# Steckkarte.net
KiCad netlist of a schematic drawn in EAGLE
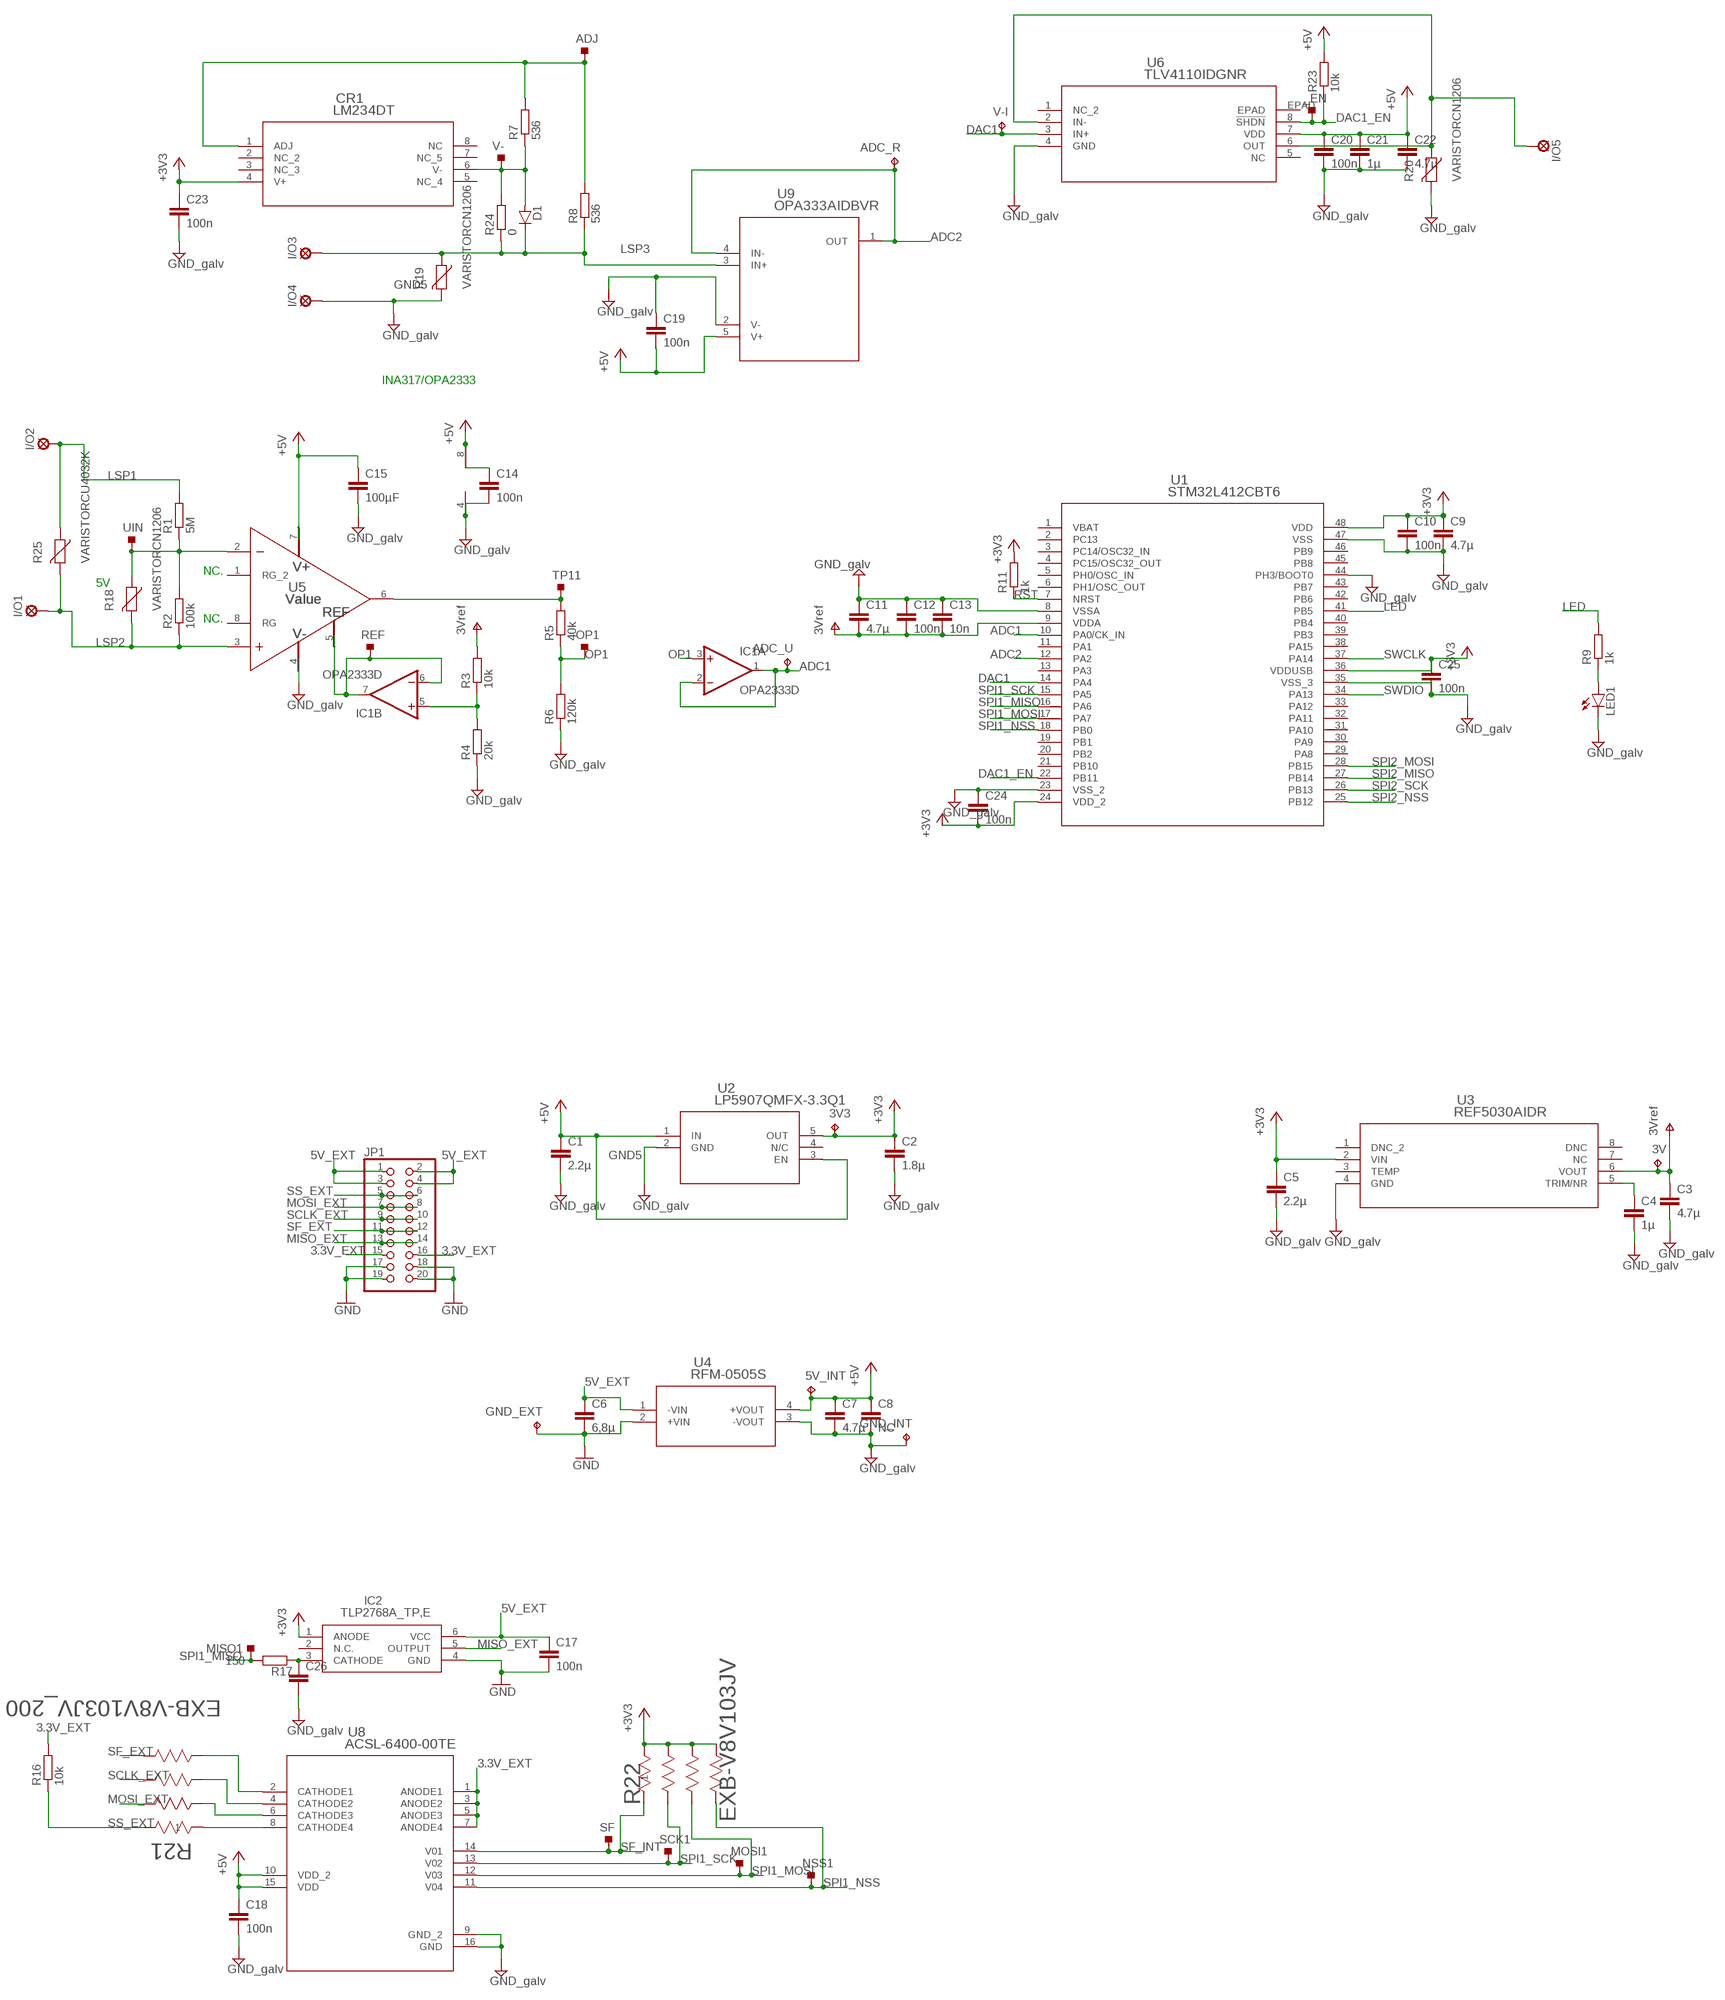
[diagram p0: schematic, sheet 1, part 1 of 2]
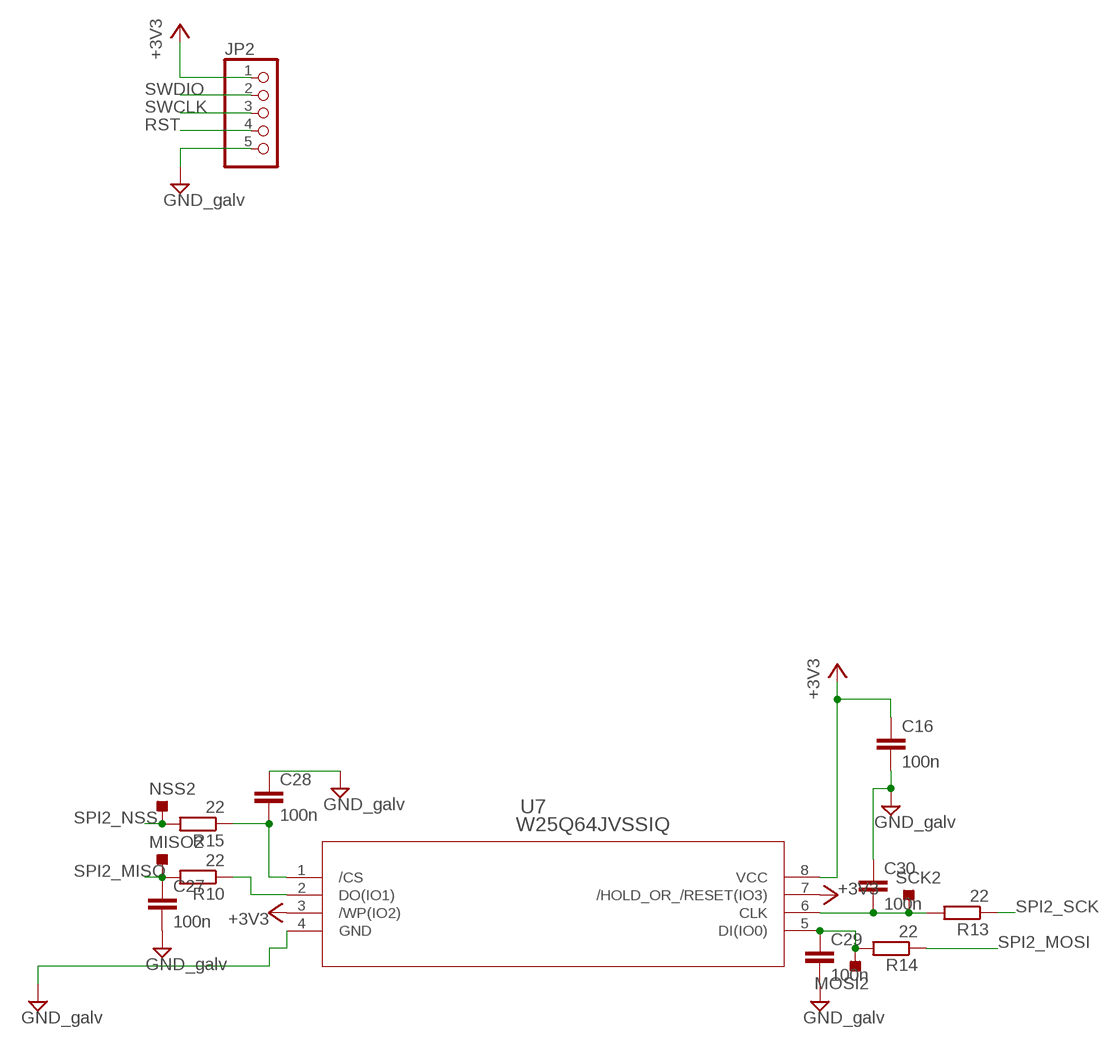
[diagram p1: schematic, sheet 1, part 2 of 2]

(export (version "E")
  (design (tool "Eeschema 10.0.6"))
  (components
    (comp (ref "3V")
      (value "TPPAD1-13")
      (footprint "eagle-import:P1-13")
      (libsource (lib "eagle-import") (part "TPPAD1-13"))
    )
    (comp (ref "3V3")
      (value "TPPAD1-13")
      (footprint "eagle-import:P1-13")
      (libsource (lib "eagle-import") (part "TPPAD1-13"))
    )
    (comp (ref "5V_INT")
      (value "TPPAD1-13")
      (footprint "eagle-import:P1-13")
      (libsource (lib "eagle-import") (part "TPPAD1-13"))
    )
    (comp (ref "ADC_R")
      (value "TPPAD1-13")
      (footprint "eagle-import:P1-13")
      (libsource (lib "eagle-import") (part "TPPAD1-13"))
    )
    (comp (ref "ADC_U")
      (value "TPPAD1-13")
      (footprint "eagle-import:P1-13")
      (libsource (lib "eagle-import") (part "TPPAD1-13"))
    )
    (comp (ref "ADJ")
      (value "TESTPOINT_TPS-SMD-10SN")
      (footprint "eagle-import:TESTPOINT_SMD-10SN")
      (libsource (lib "eagle-import") (part "TESTPOINT_TPS-SMD-10SN"))
    )
    (comp (ref "C1")
      (value "2.2µ")
      (footprint "eagle-import:C0603K")
      (libsource (lib "eagle-import") (part "C-EUC0603K"))
    )
    (comp (ref "C2")
      (value "1.8µ")
      (footprint "eagle-import:C1206K")
      (libsource (lib "eagle-import") (part "C-EUC1206K"))
    )
    (comp (ref "C3")
      (value "4.7µ")
      (footprint "eagle-import:C0603K")
      (libsource (lib "eagle-import") (part "C-EUC0603K"))
    )
    (comp (ref "C4")
      (value "1µ")
      (footprint "eagle-import:C0603K")
      (libsource (lib "eagle-import") (part "C-EUC0603K"))
    )
    (comp (ref "C5")
      (value "2.2µ")
      (footprint "eagle-import:C0603K")
      (libsource (lib "eagle-import") (part "C-EUC0603K"))
    )
    (comp (ref "C6")
      (value "6,8µ")
      (footprint "eagle-import:C0603K")
      (libsource (lib "eagle-import") (part "resistor_348_C-EUC0603K"))
    )
    (comp (ref "C7")
      (value "4.7µ")
      (footprint "eagle-import:C0603K")
      (libsource (lib "eagle-import") (part "resistor_348_C-EUC0603K"))
    )
    (comp (ref "C8")
      (value "NC")
      (footprint "eagle-import:C0603K")
      (libsource (lib "eagle-import") (part "resistor_348_C-EUC0603K"))
    )
    (comp (ref "C9")
      (value "4.7µ")
      (footprint "eagle-import:C0603K")
      (libsource (lib "eagle-import") (part "C-EUC0603K"))
    )
    (comp (ref "C10")
      (value "100n")
      (footprint "eagle-import:C0603K")
      (libsource (lib "eagle-import") (part "C-EUC0603K"))
    )
    (comp (ref "C11")
      (value "4.7µ")
      (footprint "eagle-import:C0603K")
      (libsource (lib "eagle-import") (part "C-EUC0603K"))
    )
    (comp (ref "C12")
      (value "100n")
      (footprint "eagle-import:C0603K")
      (libsource (lib "eagle-import") (part "C-EUC0603K"))
    )
    (comp (ref "C13")
      (value "10n")
      (footprint "eagle-import:C0603K")
      (libsource (lib "eagle-import") (part "C-EUC0603K"))
    )
    (comp (ref "C14")
      (value "100n")
      (footprint "eagle-import:C0603K")
      (libsource (lib "eagle-import") (part "C-EUC0603K"))
    )
    (comp (ref "C15")
      (value "100µF")
      (footprint "eagle-import:C1206K")
      (libsource (lib "eagle-import") (part "resistor_348_C-EUC1206K"))
    )
    (comp (ref "C16")
      (value "100n")
      (footprint "eagle-import:C0603K")
      (libsource (lib "eagle-import") (part "C-EUC0603K"))
    )
    (comp (ref "C17")
      (value "100n")
      (footprint "eagle-import:C0603K")
      (libsource (lib "eagle-import") (part "C-EUC0603K"))
    )
    (comp (ref "C18")
      (value "100n")
      (footprint "eagle-import:C0603K")
      (libsource (lib "eagle-import") (part "C-EUC0603K"))
    )
    (comp (ref "C19")
      (value "100n")
      (footprint "eagle-import:C0603K")
      (libsource (lib "eagle-import") (part "C-EUC0603K"))
    )
    (comp (ref "C20")
      (value "100n")
      (footprint "eagle-import:C0603K")
      (libsource (lib "eagle-import") (part "C-EUC0603K"))
    )
    (comp (ref "C21")
      (value "1µ")
      (footprint "eagle-import:C0603K")
      (libsource (lib "eagle-import") (part "C-EUC0603K"))
    )
    (comp (ref "C22")
      (value "4.7µ")
      (footprint "eagle-import:C0603K")
      (libsource (lib "eagle-import") (part "C-EUC0603K"))
    )
    (comp (ref "C23")
      (value "100n")
      (footprint "eagle-import:C0603K")
      (libsource (lib "eagle-import") (part "C-EUC0603K"))
    )
    (comp (ref "C24")
      (value "100n")
      (footprint "eagle-import:C0603K")
      (libsource (lib "eagle-import") (part "C-EUC0603K"))
    )
    (comp (ref "C25")
      (value "100n")
      (footprint "eagle-import:C0603K")
      (libsource (lib "eagle-import") (part "C-EUC0603K"))
    )
    (comp (ref "C26")
      (value "C-EUC0603K")
      (footprint "eagle-import:C0603K")
      (libsource (lib "eagle-import") (part "C-EUC0603K"))
    )
    (comp (ref "C27")
      (value "100n")
      (footprint "eagle-import:C0603K")
      (libsource (lib "eagle-import") (part "C-EUC0603K"))
    )
    (comp (ref "C28")
      (value "100n")
      (footprint "eagle-import:C0603K")
      (libsource (lib "eagle-import") (part "C-EUC0603K"))
    )
    (comp (ref "C29")
      (value "100n")
      (footprint "eagle-import:C0603K")
      (libsource (lib "eagle-import") (part "C-EUC0603K"))
    )
    (comp (ref "C30")
      (value "100n")
      (footprint "eagle-import:C0603K")
      (libsource (lib "eagle-import") (part "C-EUC0603K"))
    )
    (comp (ref "CR1")
      (value "LM234DT")
      (footprint "eagle-import:SO-8")
      (libsource (lib "eagle-import") (part "LM234DT"))
    )
    (comp (ref "D1")
      (value "D-SOD123")
      (footprint "eagle-import:SOD123")
      (libsource (lib "eagle-import") (part "D-SOD123"))
    )
    (comp (ref "GND_EXT")
      (value "TPPAD1-13")
      (footprint "eagle-import:P1-13")
      (libsource (lib "eagle-import") (part "TPPAD1-13"))
    )
    (comp (ref "GND_INT")
      (value "TPPAD1-13")
      (footprint "eagle-import:P1-13")
      (libsource (lib "eagle-import") (part "TPPAD1-13"))
    )
    (comp (ref "I/O1")
      (value "SE14")
      (footprint "eagle-import:SE14")
      (libsource (lib "eagle-import") (part "SE14"))
    )
    (comp (ref "I/O2")
      (value "SE14")
      (footprint "eagle-import:SE14")
      (libsource (lib "eagle-import") (part "SE14"))
    )
    (comp (ref "I/O3")
      (value "SE14")
      (footprint "eagle-import:SE14")
      (libsource (lib "eagle-import") (part "SE14"))
    )
    (comp (ref "I/O4")
      (value "SE14")
      (footprint "eagle-import:SE14")
      (libsource (lib "eagle-import") (part "SE14"))
    )
    (comp (ref "I/O5")
      (value "SE14")
      (footprint "eagle-import:SE14")
      (libsource (lib "eagle-import") (part "SE14"))
    )
    (comp (ref "IC1")
      (value "OPA2333D")
      (footprint "eagle-import:SO08")
      (libsource (lib "eagle-import") (part "OPA2333D"))
    )
    (comp (ref "IC2")
      (value "TLP2768A_TP,E")
      (footprint "eagle-import:SOIC127P1000X220-6N")
      (fields
        (field (name "MANUFACTURER_PART_NUMBER") "TLP2768A(TP,E")
        (field (name "MOUSER_PART_NUMBER") "757-TLP2768ATPE")
      )
      (libsource (lib "eagle-import") (part "TLP2768A_TP,E"))
    )
    (comp (ref "JP1")
      (value "PINHD-2X10/90")
      (footprint "eagle-import:2X10_90")
      (libsource (lib "eagle-import") (part "PINHD-2X10/90"))
    )
    (comp (ref "JP2")
      (value "PINHD-1X5")
      (footprint "eagle-import:1X05")
      (libsource (lib "eagle-import") (part "PINHD-1X5"))
    )
    (comp (ref "LED1")
      (value "LED5MM")
      (footprint "eagle-import:LED5MM")
      (libsource (lib "eagle-import") (part "LED5MM"))
    )
    (comp (ref "MISO1")
      (value "TESTPOINT_TPS-SMD-10SN")
      (footprint "eagle-import:TESTPOINT_SMD-10SN")
      (libsource (lib "eagle-import") (part "TESTPOINT_TPS-SMD-10SN"))
    )
    (comp (ref "MISO2")
      (value "TESTPOINT_TPS-SMD-10SN")
      (footprint "eagle-import:TESTPOINT_SMD-10SN")
      (libsource (lib "eagle-import") (part "TESTPOINT_TPS-SMD-10SN"))
    )
    (comp (ref "MOSI1")
      (value "TESTPOINT_TPS-SMD-10SN")
      (footprint "eagle-import:TESTPOINT_SMD-10SN")
      (libsource (lib "eagle-import") (part "TESTPOINT_TPS-SMD-10SN"))
    )
    (comp (ref "MOSI2")
      (value "TESTPOINT_TPS-SMD-10SN")
      (footprint "eagle-import:TESTPOINT_SMD-10SN")
      (libsource (lib "eagle-import") (part "TESTPOINT_TPS-SMD-10SN"))
    )
    (comp (ref "NSS1")
      (value "TESTPOINT_TPS-SMD-10SN")
      (footprint "eagle-import:TESTPOINT_SMD-10SN")
      (libsource (lib "eagle-import") (part "TESTPOINT_TPS-SMD-10SN"))
    )
    (comp (ref "NSS2")
      (value "TESTPOINT_TPS-SMD-10SN")
      (footprint "eagle-import:TESTPOINT_SMD-10SN")
      (libsource (lib "eagle-import") (part "TESTPOINT_TPS-SMD-10SN"))
    )
    (comp (ref "OP1")
      (value "TESTPOINT_TPS-SMD-10SN")
      (footprint "eagle-import:TESTPOINT_SMD-10SN")
      (libsource (lib "eagle-import") (part "TESTPOINT_TPS-SMD-10SN"))
    )
    (comp (ref "R1")
      (value "5M")
      (footprint "eagle-import:R1206")
      (libsource (lib "eagle-import") (part "R-EU_R1206"))
    )
    (comp (ref "R2")
      (value "100k")
      (footprint "eagle-import:R1206")
      (libsource (lib "eagle-import") (part "R-EU_R1206"))
    )
    (comp (ref "R3")
      (value "10k")
      (footprint "eagle-import:R0603")
      (libsource (lib "eagle-import") (part "R-EU_R0603"))
    )
    (comp (ref "R4")
      (value "20k")
      (footprint "eagle-import:R0603")
      (libsource (lib "eagle-import") (part "R-EU_R0603"))
    )
    (comp (ref "R5")
      (value "40k")
      (footprint "eagle-import:R0603")
      (libsource (lib "eagle-import") (part "R-EU_R0603"))
    )
    (comp (ref "R6")
      (value "120k")
      (footprint "eagle-import:R0603")
      (libsource (lib "eagle-import") (part "R-EU_R0603"))
    )
    (comp (ref "R7")
      (value "536")
      (footprint "eagle-import:R0603")
      (libsource (lib "eagle-import") (part "R-EU_R0603"))
    )
    (comp (ref "R8")
      (value "536")
      (footprint "eagle-import:R0603")
      (libsource (lib "eagle-import") (part "R-EU_R0603"))
    )
    (comp (ref "R9")
      (value "1k")
      (footprint "eagle-import:R0603")
      (libsource (lib "eagle-import") (part "R-EU_R0603"))
    )
    (comp (ref "R10")
      (value "22")
      (footprint "eagle-import:R0603")
      (libsource (lib "eagle-import") (part "R-EU_R0603"))
    )
    (comp (ref "R11")
      (value "1k")
      (footprint "eagle-import:R0603")
      (libsource (lib "eagle-import") (part "R-EU_R0603"))
    )
    (comp (ref "R13")
      (value "22")
      (footprint "eagle-import:R0603")
      (libsource (lib "eagle-import") (part "R-EU_R0603"))
    )
    (comp (ref "R14")
      (value "22")
      (footprint "eagle-import:R0603")
      (libsource (lib "eagle-import") (part "R-EU_R0603"))
    )
    (comp (ref "R15")
      (value "22")
      (footprint "eagle-import:R0603")
      (libsource (lib "eagle-import") (part "R-EU_R0603"))
    )
    (comp (ref "R16")
      (value "10k")
      (footprint "eagle-import:R0603")
      (libsource (lib "eagle-import") (part "R-EU_R0603"))
    )
    (comp (ref "R17")
      (value "150")
      (footprint "eagle-import:R0603")
      (libsource (lib "eagle-import") (part "R-EU_R0603"))
    )
    (comp (ref "R18")
      (value "VARISTORCN1206")
      (footprint "eagle-import:CT_CN1206")
      (libsource (lib "eagle-import") (part "VARISTORCN1206"))
    )
    (comp (ref "R19")
      (value "VARISTORCN1206")
      (footprint "eagle-import:CT_CN1206")
      (libsource (lib "eagle-import") (part "VARISTORCN1206"))
    )
    (comp (ref "R20")
      (value "VARISTORCN1206")
      (footprint "eagle-import:CT_CN1206")
      (libsource (lib "eagle-import") (part "VARISTORCN1206"))
    )
    (comp (ref "R21")
      (value "EXB-V8V103JV_200")
      (footprint "eagle-import:EXBV8V")
      (fields (field (name "MANUFACTURER_PART_NUMBER") "EXB-V8V103JV"))
      (libsource (lib "eagle-import") (part "EXB-V8V103JV"))
    )
    (comp (ref "R22")
      (value "EXB-V8V103JV")
      (footprint "eagle-import:EXBV8V")
      (libsource (lib "eagle-import") (part "EXB-V8V103JV"))
    )
    (comp (ref "R23")
      (value "10k")
      (footprint "eagle-import:R0603")
      (libsource (lib "eagle-import") (part "R-EU_R0603"))
    )
    (comp (ref "R24")
      (value "0")
      (footprint "eagle-import:R0603")
      (libsource (lib "eagle-import") (part "R-EU_R0603"))
    )
    (comp (ref "R25")
      (value "VARISTORCU4032K")
      (footprint "eagle-import:CU4032K")
      (libsource (lib "eagle-import") (part "VARISTORCU4032K"))
    )
    (comp (ref "REF")
      (value "TESTPOINT_TPS-SMD-10SN")
      (footprint "eagle-import:TESTPOINT_SMD-10SN")
      (libsource (lib "eagle-import") (part "TESTPOINT_TPS-SMD-10SN"))
    )
    (comp (ref "SCK1")
      (value "TESTPOINT_TPS-SMD-10SN")
      (footprint "eagle-import:TESTPOINT_SMD-10SN")
      (libsource (lib "eagle-import") (part "TESTPOINT_TPS-SMD-10SN"))
    )
    (comp (ref "SCK2")
      (value "TESTPOINT_TPS-SMD-10SN")
      (footprint "eagle-import:TESTPOINT_SMD-10SN")
      (libsource (lib "eagle-import") (part "TESTPOINT_TPS-SMD-10SN"))
    )
    (comp (ref "SF")
      (value "TESTPOINT_TPS-SMD-10SN")
      (footprint "eagle-import:TESTPOINT_SMD-10SN")
      (libsource (lib "eagle-import") (part "TESTPOINT_TPS-SMD-10SN"))
    )
    (comp (ref "TP11")
      (value "TESTPOINT_TPS-SMD-10SN")
      (footprint "eagle-import:TESTPOINT_SMD-10SN")
      (libsource (lib "eagle-import") (part "TESTPOINT_TPS-SMD-10SN"))
    )
    (comp (ref "U1")
      (value "STM32L412CBT6")
      (footprint "eagle-import:LQFP-48")
      (fields (field (name "COPYRIGHT") "Copyright (C) 2018 Accelerated Designs. All rights reserved"))
      (libsource (lib "eagle-import") (part "STM32L412CBT6"))
    )
    (comp (ref "U2")
      (value "LP5907QMFX-3.3Q1")
      (footprint "eagle-import:DBV5")
      (libsource (lib "eagle-import") (part "LP5907QMFX-3.3Q1"))
    )
    (comp (ref "U3")
      (value "REF5030AIDR")
      (footprint "eagle-import:D8")
      (libsource (lib "eagle-import") (part "REF5030AIDR"))
    )
    (comp (ref "U4")
      (value "RFM-0505S")
      (footprint "eagle-import:RFM-0505S")
      (fields (field (name "COPYRIGHT") "Copyright (C) 2018 Accelerated Designs. All rights reserved"))
      (libsource (lib "eagle-import") (part "RFM-0505S"))
    )
    (comp (ref "U5")
      (value "Value")
      (footprint "eagle-import:DGK0008A_N")
      (fields (field (name "MANUFACTURER") "Texas Instruments") (field (name "PARTNUMBER") "INA317IDGKR"))
      (libsource (lib "eagle-import") (part "INA317IDGKR"))
    )
    (comp (ref "U6")
      (value "TLV4110IDGNR")
      (footprint "eagle-import:DGN8_1P89X1P57")
      (fields
        (field (name "GENERIC_PART_NUMBER") "TLV4110")
        (field (name "MANUFACTURER") "Texas Instruments")
      )
      (libsource (lib "eagle-import") (part "TLV4110IDGNR"))
    )
    (comp (ref "U7")
      (value "W25Q64JVSSIQ")
      (footprint "eagle-import:SOIC-8_5P28X5P28")
      (fields (field (name "COPYRIGHT") "Copyright (C) 2018 Accelerated Designs. All rights reserved"))
      (libsource (lib "eagle-import") (part "W25Q64JVSSIQ"))
    )
    (comp (ref "U8")
      (value "ACSL-6400-00TE")
      (footprint "eagle-import:SOIC_6400-00TE")
      (fields (field (name "COPYRIGHT") "Copyright (C) 2018 Accelerated Designs. All rights reserved"))
      (libsource (lib "eagle-import") (part "ACSL-6400-00TE"))
    )
    (comp (ref "U9")
      (value "OPA333AIDBVR")
      (footprint "eagle-import:DBV5")
      (fields (field (name "GENERIC_PART_NUMBER") "OPA333") (field (name "MANUFACTURER") "Texas Instruments"))
      (libsource (lib "eagle-import") (part "OPA333AIDBVR"))
    )
    (comp (ref "UIN")
      (value "TESTPOINT_TPS-SMD-10SN")
      (footprint "eagle-import:TESTPOINT_SMD-10SN")
      (libsource (lib "eagle-import") (part "TESTPOINT_TPS-SMD-10SN"))
    )
    (comp (ref "V-")
      (value "TESTPOINT_TPS-SMD-10SN")
      (footprint "eagle-import:TESTPOINT_SMD-10SN")
      (libsource (lib "eagle-import") (part "TESTPOINT_TPS-SMD-10SN"))
    )
    (comp (ref "V-I")
      (value "TPPAD1-13")
      (footprint "eagle-import:P1-13")
      (libsource (lib "eagle-import") (part "TPPAD1-13"))
    )
    (comp (ref "_EN")
      (value "TESTPOINT_TPS-SMD-10SN")
      (footprint "eagle-import:TESTPOINT_SMD-10SN")
      (libsource (lib "eagle-import") (part "TESTPOINT_TPS-SMD-10SN"))
    )
  )
  (nets
    (net (code "1") (name "+3V3") (class "Default")
      (node (ref "3V3") (pin "TP") (pinfunction "TP_TP") (pintype "input"))
      (node (ref "C10") (pin "1") (pinfunction "1_1") (pintype "passive"))
      (node (ref "C16") (pin "1") (pinfunction "1_1") (pintype "passive"))
      (node (ref "C2") (pin "1") (pinfunction "1_1") (pintype "passive"))
      (node (ref "C23") (pin "1") (pinfunction "1_1") (pintype "passive"))
      (node (ref "C24") (pin "2") (pinfunction "2_2") (pintype "passive"))
      (node (ref "C25") (pin "1") (pinfunction "1_1") (pintype "passive"))
      (node (ref "C5") (pin "1") (pinfunction "1_1") (pintype "passive"))
      (node (ref "C9") (pin "1") (pinfunction "1_1") (pintype "passive"))
      (node (ref "CR1") (pin "4") (pinfunction "V+_4") (pintype "power_in"))
      (node (ref "IC2") (pin "1") (pinfunction "ANODE_1") (pintype "bidirectional"))
      (node (ref "JP2") (pin "1") (pinfunction "1_1") (pintype "passive"))
      (node (ref "R11") (pin "2") (pinfunction "2_2") (pintype "passive"))
      (node (ref "R22") (pin "5") (pinfunction "5_5") (pintype "passive"))
      (node (ref "R22") (pin "6") (pinfunction "6_6") (pintype "passive"))
      (node (ref "R22") (pin "7") (pinfunction "7_7") (pintype "passive"))
      (node (ref "R22") (pin "8") (pinfunction "8_8") (pintype "passive"))
      (node (ref "U1") (pin "24") (pinfunction "VDD_2_24") (pintype "power_in"))
      (node (ref "U1") (pin "36") (pinfunction "VDDUSB_36") (pintype "power_in"))
      (node (ref "U1") (pin "48") (pinfunction "VDD_48") (pintype "power_in"))
      (node (ref "U2") (pin "5") (pinfunction "OUT_5") (pintype "output"))
      (node (ref "U3") (pin "2") (pinfunction "VIN_2") (pintype "input"))
      (node (ref "U7") (pin "3") (pinfunction "/WP(IO2)_3") (pintype "passive"))
      (node (ref "U7") (pin "7") (pinfunction "/HOLD_OR_/RESET(IO3)_7") (pintype "passive"))
      (node (ref "U7") (pin "8") (pinfunction "VCC_8") (pintype "power_in"))
    )
    (net (code "2") (name "+5V") (class "Default")
      (node (ref "5V_INT") (pin "TP") (pinfunction "TP_TP") (pintype "input"))
      (node (ref "C1") (pin "1") (pinfunction "1_1") (pintype "passive"))
      (node (ref "C14") (pin "1") (pinfunction "1_1") (pintype "passive"))
      (node (ref "C15") (pin "1") (pinfunction "1_1") (pintype "passive"))
      (node (ref "C18") (pin "1") (pinfunction "1_1") (pintype "passive"))
      (node (ref "C19") (pin "2") (pinfunction "2_2") (pintype "passive"))
      (node (ref "C20") (pin "1") (pinfunction "1_1") (pintype "passive"))
      (node (ref "C21") (pin "1") (pinfunction "1_1") (pintype "passive"))
      (node (ref "C22") (pin "1") (pinfunction "1_1") (pintype "passive"))
      (node (ref "C7") (pin "1") (pinfunction "1_1") (pintype "passive"))
      (node (ref "C8") (pin "1") (pinfunction "1_1") (pintype "passive"))
      (node (ref "IC1") (pin "8") (pinfunction "V+_8") (pintype "power_in"))
      (node (ref "R23") (pin "2") (pinfunction "2_2") (pintype "passive"))
      (node (ref "U2") (pin "1") (pinfunction "IN_1") (pintype "input"))
      (node (ref "U2") (pin "3") (pinfunction "EN_3") (pintype "input"))
      (node (ref "U4") (pin "4") (pinfunction "+VOUT_4") (pintype "output"))
      (node (ref "U5") (pin "7") (pinfunction "V+_7") (pintype "power_in"))
      (node (ref "U6") (pin "7") (pinfunction "VDD_7") (pintype "power_in"))
      (node (ref "U8") (pin "10") (pinfunction "VDD_2_10") (pintype "power_in"))
      (node (ref "U8") (pin "15") (pinfunction "VDD_15") (pintype "power_in"))
      (node (ref "U9") (pin "5") (pinfunction "V+_5") (pintype "power_in"))
    )
    (net (code "3") (name "/3.3V_EXT") (class "Default")
      (node (ref "JP1") (pin "15") (pinfunction "15_15") (pintype "passive"))
      (node (ref "JP1") (pin "16") (pinfunction "16_16") (pintype "passive"))
      (node (ref "R16") (pin "2") (pinfunction "2_2") (pintype "passive"))
      (node (ref "U8") (pin "1") (pinfunction "ANODE1_1") (pintype "bidirectional"))
      (node (ref "U8") (pin "3") (pinfunction "ANODE2_3") (pintype "bidirectional"))
      (node (ref "U8") (pin "5") (pinfunction "ANODE3_5") (pintype "bidirectional"))
      (node (ref "U8") (pin "7") (pinfunction "ANODE4_7") (pintype "bidirectional"))
    )
    (net (code "4") (name "/5V_EXT") (class "Default")
      (node (ref "C17") (pin "1") (pinfunction "1_1") (pintype "passive"))
      (node (ref "C6") (pin "1") (pinfunction "1_1") (pintype "passive"))
      (node (ref "IC2") (pin "6") (pinfunction "VCC_6") (pintype "bidirectional"))
      (node (ref "JP1") (pin "1") (pinfunction "1_1") (pintype "passive"))
      (node (ref "JP1") (pin "2") (pinfunction "2_2") (pintype "passive"))
      (node (ref "JP1") (pin "3") (pinfunction "3_3") (pintype "passive"))
      (node (ref "JP1") (pin "4") (pinfunction "4_4") (pintype "passive"))
      (node (ref "U4") (pin "1") (pinfunction "-VIN_1") (pintype "input"))
    )
    (net (code "5") (name "/ADC1") (class "Default")
      (node (ref "ADC_U") (pin "TP") (pinfunction "TP_TP") (pintype "input"))
      (node (ref "IC1") (pin "1") (pinfunction "OUT_1") (pintype "output"))
      (node (ref "IC1") (pin "2") (pinfunction "-IN_2") (pintype "input"))
      (node (ref "U1") (pin "10") (pinfunction "PA0/CK_IN_10") (pintype "bidirectional"))
    )
    (net (code "6") (name "/ADC2") (class "Default")
      (node (ref "ADC_R") (pin "TP") (pinfunction "TP_TP") (pintype "input"))
      (node (ref "U1") (pin "12") (pinfunction "PA2_12") (pintype "bidirectional"))
      (node (ref "U9") (pin "1") (pinfunction "OUT_1") (pintype "output"))
      (node (ref "U9") (pin "4") (pinfunction "IN-_4") (pintype "input"))
    )
    (net (code "7") (name "/DAC1") (class "Default")
      (node (ref "U1") (pin "14") (pinfunction "PA4_14") (pintype "bidirectional"))
      (node (ref "U6") (pin "3") (pinfunction "IN+_3") (pintype "input"))
      (node (ref "V-I") (pin "TP") (pinfunction "TP_TP") (pintype "input"))
    )
    (net (code "8") (name "/DAC1_EN") (class "Default")
      (node (ref "R23") (pin "1") (pinfunction "1_1") (pintype "passive"))
      (node (ref "U1") (pin "22") (pinfunction "PB11_22") (pintype "bidirectional"))
      (node (ref "U6") (pin "8") (pinfunction "~{SHDN}_8") (pintype "passive"))
      (node (ref "_EN") (pin "TP") (pinfunction "TP_TP") (pintype "passive"))
    )
    (net (code "9") (name "/LED") (class "Default")
      (node (ref "R9") (pin "2") (pinfunction "2_2") (pintype "passive"))
      (node (ref "U1") (pin "41") (pinfunction "PB5_41") (pintype "bidirectional"))
    )
    (net (code "10") (name "/LSP1") (class "Default")
      (node (ref "I/O2") (pin "MP") (pinfunction "MP_MP") (pintype "passive"))
      (node (ref "R1") (pin "2") (pinfunction "2_2") (pintype "passive"))
      (node (ref "R25") (pin "1") (pinfunction "1_1") (pintype "passive"))
    )
    (net (code "11") (name "/LSP2") (class "Default")
      (node (ref "I/O1") (pin "MP") (pinfunction "MP_MP") (pintype "passive"))
      (node (ref "R18") (pin "2") (pinfunction "2_2") (pintype "passive"))
      (node (ref "R2") (pin "1") (pinfunction "1_1") (pintype "passive"))
      (node (ref "R25") (pin "2") (pinfunction "2_2") (pintype "passive"))
      (node (ref "U5") (pin "3") (pinfunction "IN+_3") (pintype "input"))
    )
    (net (code "12") (name "/LSP3") (class "Default")
      (node (ref "D1") (pin "1") (pinfunction "C_1") (pintype "passive"))
      (node (ref "I/O3") (pin "MP") (pinfunction "MP_MP") (pintype "passive"))
      (node (ref "R19") (pin "1") (pinfunction "1_1") (pintype "passive"))
      (node (ref "R24") (pin "1") (pinfunction "1_1") (pintype "passive"))
      (node (ref "R8") (pin "1") (pinfunction "1_1") (pintype "passive"))
      (node (ref "U9") (pin "3") (pinfunction "IN+_3") (pintype "input"))
    )
    (net (code "13") (name "/MISO_EXT") (class "Default")
      (node (ref "IC2") (pin "5") (pinfunction "OUTPUT_5") (pintype "bidirectional"))
      (node (ref "JP1") (pin "13") (pinfunction "13_13") (pintype "passive"))
      (node (ref "JP1") (pin "14") (pinfunction "14_14") (pintype "passive"))
    )
    (net (code "14") (name "/MOSI_EXT") (class "Default")
      (node (ref "JP1") (pin "7") (pinfunction "7_7") (pintype "passive"))
      (node (ref "JP1") (pin "8") (pinfunction "8_8") (pintype "passive"))
      (node (ref "R21") (pin "7") (pinfunction "7_7") (pintype "passive"))
    )
    (net (code "15") (name "/OP1") (class "Default")
      (node (ref "IC1") (pin "3") (pinfunction "+IN_3") (pintype "input"))
      (node (ref "OP1") (pin "TP") (pinfunction "TP_TP") (pintype "passive"))
      (node (ref "R5") (pin "1") (pinfunction "1_1") (pintype "passive"))
      (node (ref "R6") (pin "2") (pinfunction "2_2") (pintype "passive"))
    )
    (net (code "16") (name "/RST") (class "Default")
      (node (ref "JP2") (pin "4") (pinfunction "4_4") (pintype "passive"))
      (node (ref "R11") (pin "1") (pinfunction "1_1") (pintype "passive"))
      (node (ref "U1") (pin "7") (pinfunction "NRST_7") (pintype "bidirectional"))
    )
    (net (code "17") (name "/SCLK_EXT") (class "Default")
      (node (ref "JP1") (pin "10") (pinfunction "10_10") (pintype "passive"))
      (node (ref "JP1") (pin "9") (pinfunction "9_9") (pintype "passive"))
      (node (ref "R21") (pin "6") (pinfunction "6_6") (pintype "passive"))
    )
    (net (code "18") (name "/SF_EXT") (class "Default")
      (node (ref "JP1") (pin "11") (pinfunction "11_11") (pintype "passive"))
      (node (ref "JP1") (pin "12") (pinfunction "12_12") (pintype "passive"))
      (node (ref "R21") (pin "5") (pinfunction "5_5") (pintype "passive"))
    )
    (net (code "19") (name "/SF_INT") (class "Default")
      (node (ref "R22") (pin "1") (pinfunction "1_1") (pintype "passive"))
      (node (ref "SF") (pin "TP") (pinfunction "TP_TP") (pintype "passive"))
      (node (ref "U8") (pin "14") (pinfunction "V01_14") (pintype "bidirectional"))
    )
    (net (code "20") (name "/SPI1_MISO") (class "Default")
      (node (ref "MISO1") (pin "TP") (pinfunction "TP_TP") (pintype "passive"))
      (node (ref "R17") (pin "2") (pinfunction "2_2") (pintype "passive"))
      (node (ref "U1") (pin "16") (pinfunction "PA6_16") (pintype "bidirectional"))
    )
    (net (code "21") (name "/SPI1_MOSI") (class "Default")
      (node (ref "MOSI1") (pin "TP") (pinfunction "TP_TP") (pintype "passive"))
      (node (ref "R22") (pin "3") (pinfunction "3_3") (pintype "passive"))
      (node (ref "U1") (pin "17") (pinfunction "PA7_17") (pintype "bidirectional"))
      (node (ref "U8") (pin "12") (pinfunction "V03_12") (pintype "bidirectional"))
    )
    (net (code "22") (name "/SPI1_NSS") (class "Default")
      (node (ref "NSS1") (pin "TP") (pinfunction "TP_TP") (pintype "passive"))
      (node (ref "R22") (pin "4") (pinfunction "4_4") (pintype "passive"))
      (node (ref "U1") (pin "18") (pinfunction "PB0_18") (pintype "bidirectional"))
      (node (ref "U8") (pin "11") (pinfunction "V04_11") (pintype "bidirectional"))
    )
    (net (code "23") (name "/SPI1_SCK") (class "Default")
      (node (ref "R22") (pin "2") (pinfunction "2_2") (pintype "passive"))
      (node (ref "SCK1") (pin "TP") (pinfunction "TP_TP") (pintype "passive"))
      (node (ref "U1") (pin "15") (pinfunction "PA5_15") (pintype "bidirectional"))
      (node (ref "U8") (pin "13") (pinfunction "V02_13") (pintype "bidirectional"))
    )
    (net (code "24") (name "/SPI2_MISO") (class "Default")
      (node (ref "C27") (pin "1") (pinfunction "1_1") (pintype "passive"))
      (node (ref "MISO2") (pin "TP") (pinfunction "TP_TP") (pintype "passive"))
      (node (ref "R10") (pin "2") (pinfunction "2_2") (pintype "passive"))
      (node (ref "U1") (pin "27") (pinfunction "PB14_27") (pintype "bidirectional"))
    )
    (net (code "25") (name "/SPI2_MOSI") (class "Default")
      (node (ref "R14") (pin "1") (pinfunction "1_1") (pintype "passive"))
      (node (ref "U1") (pin "28") (pinfunction "PB15_28") (pintype "bidirectional"))
    )
    (net (code "26") (name "/SPI2_NSS") (class "Default")
      (node (ref "NSS2") (pin "TP") (pinfunction "TP_TP") (pintype "passive"))
      (node (ref "R15") (pin "2") (pinfunction "2_2") (pintype "passive"))
      (node (ref "U1") (pin "25") (pinfunction "PB12_25") (pintype "bidirectional"))
    )
    (net (code "27") (name "/SPI2_SCK") (class "Default")
      (node (ref "R13") (pin "1") (pinfunction "1_1") (pintype "passive"))
      (node (ref "U1") (pin "26") (pinfunction "PB13_26") (pintype "bidirectional"))
    )
    (net (code "28") (name "/SS_EXT") (class "Default")
      (node (ref "JP1") (pin "5") (pinfunction "5_5") (pintype "passive"))
      (node (ref "JP1") (pin "6") (pinfunction "6_6") (pintype "passive"))
      (node (ref "R16") (pin "1") (pinfunction "1_1") (pintype "passive"))
      (node (ref "R21") (pin "8") (pinfunction "8_8") (pintype "passive"))
    )
    (net (code "29") (name "/SWCLK") (class "Default")
      (node (ref "JP2") (pin "3") (pinfunction "3_3") (pintype "passive"))
      (node (ref "U1") (pin "37") (pinfunction "PA14_37") (pintype "bidirectional"))
    )
    (net (code "30") (name "/SWDIO") (class "Default")
      (node (ref "JP2") (pin "2") (pinfunction "2_2") (pintype "passive"))
      (node (ref "U1") (pin "34") (pinfunction "PA13_34") (pintype "bidirectional"))
    )
    (net (code "31") (name "/VBAT") (class "Default")
      (node (ref "U1") (pin "1") (pinfunction "VBAT_1") (pintype "power_in"))
    )
    (net (code "32") (name "3Vref") (class "Default")
      (node (ref "3V") (pin "TP") (pinfunction "TP_TP") (pintype "input"))
      (node (ref "C11") (pin "2") (pinfunction "2_2") (pintype "passive"))
      (node (ref "C12") (pin "2") (pinfunction "2_2") (pintype "passive"))
      (node (ref "C13") (pin "2") (pinfunction "2_2") (pintype "passive"))
      (node (ref "C3") (pin "1") (pinfunction "1_1") (pintype "passive"))
      (node (ref "R3") (pin "2") (pinfunction "2_2") (pintype "passive"))
      (node (ref "U1") (pin "9") (pinfunction "VDDA_9") (pintype "power_in"))
      (node (ref "U3") (pin "6") (pinfunction "VOUT_6") (pintype "output"))
    )
    (net (code "33") (name "GND") (class "Default")
      (node (ref "C17") (pin "2") (pinfunction "2_2") (pintype "passive"))
      (node (ref "C6") (pin "2") (pinfunction "2_2") (pintype "passive"))
      (node (ref "GND_EXT") (pin "TP") (pinfunction "TP_TP") (pintype "input"))
      (node (ref "IC2") (pin "4") (pinfunction "GND_4") (pintype "bidirectional"))
      (node (ref "JP1") (pin "17") (pinfunction "17_17") (pintype "passive"))
      (node (ref "JP1") (pin "18") (pinfunction "18_18") (pintype "passive"))
      (node (ref "JP1") (pin "19") (pinfunction "19_19") (pintype "passive"))
      (node (ref "JP1") (pin "20") (pinfunction "20_20") (pintype "passive"))
      (node (ref "U4") (pin "2") (pinfunction "+VIN_2") (pintype "input"))
    )
    (net (code "34") (name "GND_galv") (class "Default")
      (node (ref "C1") (pin "2") (pinfunction "2_2") (pintype "passive"))
      (node (ref "C10") (pin "2") (pinfunction "2_2") (pintype "passive"))
      (node (ref "C11") (pin "1") (pinfunction "1_1") (pintype "passive"))
      (node (ref "C12") (pin "1") (pinfunction "1_1") (pintype "passive"))
      (node (ref "C13") (pin "1") (pinfunction "1_1") (pintype "passive"))
      (node (ref "C14") (pin "2") (pinfunction "2_2") (pintype "passive"))
      (node (ref "C15") (pin "2") (pinfunction "2_2") (pintype "passive"))
      (node (ref "C16") (pin "2") (pinfunction "2_2") (pintype "passive"))
      (node (ref "C18") (pin "2") (pinfunction "2_2") (pintype "passive"))
      (node (ref "C19") (pin "1") (pinfunction "1_1") (pintype "passive"))
      (node (ref "C2") (pin "2") (pinfunction "2_2") (pintype "passive"))
      (node (ref "C20") (pin "2") (pinfunction "2_2") (pintype "passive"))
      (node (ref "C21") (pin "2") (pinfunction "2_2") (pintype "passive"))
      (node (ref "C22") (pin "2") (pinfunction "2_2") (pintype "passive"))
      (node (ref "C23") (pin "2") (pinfunction "2_2") (pintype "passive"))
      (node (ref "C24") (pin "1") (pinfunction "1_1") (pintype "passive"))
      (node (ref "C25") (pin "2") (pinfunction "2_2") (pintype "passive"))
      (node (ref "C26") (pin "2") (pinfunction "2_2") (pintype "passive"))
      (node (ref "C27") (pin "2") (pinfunction "2_2") (pintype "passive"))
      (node (ref "C28") (pin "1") (pinfunction "1_1") (pintype "passive"))
      (node (ref "C29") (pin "2") (pinfunction "2_2") (pintype "passive"))
      (node (ref "C3") (pin "2") (pinfunction "2_2") (pintype "passive"))
      (node (ref "C30") (pin "1") (pinfunction "1_1") (pintype "passive"))
      (node (ref "C4") (pin "2") (pinfunction "2_2") (pintype "passive"))
      (node (ref "C5") (pin "2") (pinfunction "2_2") (pintype "passive"))
      (node (ref "C7") (pin "2") (pinfunction "2_2") (pintype "passive"))
      (node (ref "C8") (pin "2") (pinfunction "2_2") (pintype "passive"))
      (node (ref "C9") (pin "2") (pinfunction "2_2") (pintype "passive"))
      (node (ref "GND_INT") (pin "TP") (pinfunction "TP_TP") (pintype "input"))
      (node (ref "I/O4") (pin "MP") (pinfunction "MP_MP") (pintype "passive"))
      (node (ref "IC1") (pin "4") (pinfunction "V-_4") (pintype "power_in"))
      (node (ref "JP2") (pin "5") (pinfunction "5_5") (pintype "passive"))
      (node (ref "LED1") (pin "K") (pinfunction "C_K") (pintype "passive"))
      (node (ref "R19") (pin "2") (pinfunction "2_2") (pintype "passive"))
      (node (ref "R20") (pin "2") (pinfunction "2_2") (pintype "passive"))
      (node (ref "R4") (pin "1") (pinfunction "1_1") (pintype "passive"))
      (node (ref "R6") (pin "1") (pinfunction "1_1") (pintype "passive"))
      (node (ref "U1") (pin "23") (pinfunction "VSS_2_23") (pintype "power_in"))
      (node (ref "U1") (pin "35") (pinfunction "VSS_3_35") (pintype "power_in"))
      (node (ref "U1") (pin "44") (pinfunction "PH3/BOOT0_44") (pintype "bidirectional"))
      (node (ref "U1") (pin "47") (pinfunction "VSS_47") (pintype "power_in"))
      (node (ref "U1") (pin "8") (pinfunction "VSSA_8") (pintype "power_in"))
      (node (ref "U2") (pin "2") (pinfunction "GND_2") (pintype "power_in"))
      (node (ref "U3") (pin "4") (pinfunction "GND_4") (pintype "power_in"))
      (node (ref "U4") (pin "3") (pinfunction "-VOUT_3") (pintype "output"))
      (node (ref "U5") (pin "4") (pinfunction "V-_4") (pintype "power_in"))
      (node (ref "U6") (pin "4") (pinfunction "GND_4") (pintype "power_in"))
      (node (ref "U7") (pin "4") (pinfunction "GND_4") (pintype "passive"))
      (node (ref "U8") (pin "16") (pinfunction "GND_16") (pintype "passive"))
      (node (ref "U8") (pin "9") (pinfunction "GND_2_9") (pintype "passive"))
      (node (ref "U9") (pin "2") (pinfunction "V-_2") (pintype "power_in"))
    )
    (net (code "35") (name "Net-(CR1-ADJ)") (class "Default")
      (node (ref "ADJ") (pin "TP") (pinfunction "TP_TP") (pintype "passive"))
      (node (ref "CR1") (pin "1") (pinfunction "ADJ_1") (pintype "passive"))
      (node (ref "R7") (pin "2") (pinfunction "2_2") (pintype "passive"))
      (node (ref "R8") (pin "2") (pinfunction "2_2") (pintype "passive"))
    )
    (net (code "36") (name "Net-(CR1-V-)") (class "Default")
      (node (ref "CR1") (pin "6") (pinfunction "V-_6") (pintype "power_in"))
      (node (ref "D1") (pin "2") (pinfunction "A_2") (pintype "passive"))
      (node (ref "R24") (pin "2") (pinfunction "2_2") (pintype "passive"))
      (node (ref "R7") (pin "1") (pinfunction "1_1") (pintype "passive"))
      (node (ref "V-") (pin "TP") (pinfunction "TP_TP") (pintype "passive"))
    )
    (net (code "37") (name "Net-(IC1B-+IN)") (class "Default")
      (node (ref "IC1") (pin "5") (pinfunction "+IN_5") (pintype "input"))
      (node (ref "R3") (pin "1") (pinfunction "1_1") (pintype "passive"))
      (node (ref "R4") (pin "2") (pinfunction "2_2") (pintype "passive"))
    )
    (net (code "38") (name "Net-(IC1B--IN)") (class "Default")
      (node (ref "IC1") (pin "6") (pinfunction "-IN_6") (pintype "input"))
      (node (ref "IC1") (pin "7") (pinfunction "OUT_7") (pintype "output"))
      (node (ref "REF") (pin "TP") (pinfunction "TP_TP") (pintype "passive"))
      (node (ref "U5") (pin "5") (pinfunction "REF_5") (pintype "input"))
    )
    (net (code "39") (name "Net-(IC2-CATHODE)") (class "Default")
      (node (ref "C26") (pin "1") (pinfunction "1_1") (pintype "passive"))
      (node (ref "IC2") (pin "3") (pinfunction "CATHODE_3") (pintype "bidirectional"))
      (node (ref "R17") (pin "1") (pinfunction "1_1") (pintype "passive"))
    )
    (net (code "40") (name "Net-(LED1-PadA)") (class "Default")
      (node (ref "LED1") (pin "A") (pinfunction "A_A") (pintype "passive"))
      (node (ref "R9") (pin "1") (pinfunction "1_1") (pintype "passive"))
    )
    (net (code "41") (name "Net-(U3-TRIM{slash}NR)") (class "Default")
      (node (ref "C4") (pin "1") (pinfunction "1_1") (pintype "passive"))
      (node (ref "U3") (pin "5") (pinfunction "TRIM/NR_5") (pintype "passive"))
    )
    (net (code "42") (name "Net-(U5-IN-)") (class "Default")
      (node (ref "R1") (pin "1") (pinfunction "1_1") (pintype "passive"))
      (node (ref "R18") (pin "1") (pinfunction "1_1") (pintype "passive"))
      (node (ref "R2") (pin "2") (pinfunction "2_2") (pintype "passive"))
      (node (ref "U5") (pin "2") (pinfunction "IN-_2") (pintype "input"))
      (node (ref "UIN") (pin "TP") (pinfunction "TP_TP") (pintype "passive"))
    )
    (net (code "43") (name "Net-(U5-OUT)") (class "Default")
      (node (ref "R5") (pin "2") (pinfunction "2_2") (pintype "passive"))
      (node (ref "TP11") (pin "TP") (pinfunction "TP_TP") (pintype "passive"))
      (node (ref "U5") (pin "6") (pinfunction "OUT_6") (pintype "output"))
    )
    (net (code "44") (name "Net-(U6-IN-)") (class "Default")
      (node (ref "I/O5") (pin "MP") (pinfunction "MP_MP") (pintype "passive"))
      (node (ref "R20") (pin "1") (pinfunction "1_1") (pintype "passive"))
      (node (ref "U6") (pin "2") (pinfunction "IN-_2") (pintype "input"))
      (node (ref "U6") (pin "6") (pinfunction "OUT_6") (pintype "output"))
    )
    (net (code "45") (name "Net-(U7-CLK)") (class "Default")
      (node (ref "C30") (pin "2") (pinfunction "2_2") (pintype "passive"))
      (node (ref "R13") (pin "2") (pinfunction "2_2") (pintype "passive"))
      (node (ref "SCK2") (pin "TP") (pinfunction "TP_TP") (pintype "passive"))
      (node (ref "U7") (pin "6") (pinfunction "CLK_6") (pintype "passive"))
    )
    (net (code "46") (name "Net-(U7-DI(IO0))") (class "Default")
      (node (ref "C29") (pin "1") (pinfunction "1_1") (pintype "passive"))
      (node (ref "MOSI2") (pin "TP") (pinfunction "TP_TP") (pintype "passive"))
      (node (ref "R14") (pin "2") (pinfunction "2_2") (pintype "passive"))
      (node (ref "U7") (pin "5") (pinfunction "DI(IO0)_5") (pintype "passive"))
    )
    (net (code "47") (name "Net-(U7-DO(IO1))") (class "Default")
      (node (ref "R10") (pin "1") (pinfunction "1_1") (pintype "passive"))
      (node (ref "U7") (pin "2") (pinfunction "DO(IO1)_2") (pintype "passive"))
    )
    (net (code "48") (name "Net-(U7-{slash}CS)") (class "Default")
      (node (ref "C28") (pin "2") (pinfunction "2_2") (pintype "passive"))
      (node (ref "R15") (pin "1") (pinfunction "1_1") (pintype "passive"))
      (node (ref "U7") (pin "1") (pinfunction "/CS_1") (pintype "passive"))
    )
    (net (code "49") (name "Net-(U8-CATHODE1)") (class "Default")
      (node (ref "R21") (pin "4") (pinfunction "4_4") (pintype "passive"))
      (node (ref "U8") (pin "2") (pinfunction "CATHODE1_2") (pintype "bidirectional"))
    )
    (net (code "50") (name "Net-(U8-CATHODE2)") (class "Default")
      (node (ref "R21") (pin "3") (pinfunction "3_3") (pintype "passive"))
      (node (ref "U8") (pin "4") (pinfunction "CATHODE2_4") (pintype "bidirectional"))
    )
    (net (code "51") (name "Net-(U8-CATHODE3)") (class "Default")
      (node (ref "R21") (pin "2") (pinfunction "2_2") (pintype "passive"))
      (node (ref "U8") (pin "6") (pinfunction "CATHODE3_6") (pintype "bidirectional"))
    )
    (net (code "52") (name "Net-(U8-CATHODE4)") (class "Default")
      (node (ref "R21") (pin "1") (pinfunction "1_1") (pintype "passive"))
      (node (ref "U8") (pin "8") (pinfunction "CATHODE4_8") (pintype "bidirectional"))
    )
    (net (code "53") (name "unconnected-(CR1-NC-Pad8)") (class "Default")
      (node (ref "CR1") (pin "8") (pinfunction "NC_8") (pintype "no_connect"))
    )
    (net (code "54") (name "unconnected-(CR1-NC_2-Pad2)") (class "Default")
      (node (ref "CR1") (pin "2") (pinfunction "NC_2_2") (pintype "no_connect"))
    )
    (net (code "55") (name "unconnected-(CR1-NC_3-Pad3)") (class "Default")
      (node (ref "CR1") (pin "3") (pinfunction "NC_3_3") (pintype "no_connect"))
    )
    (net (code "56") (name "unconnected-(CR1-NC_4-Pad5)") (class "Default")
      (node (ref "CR1") (pin "5") (pinfunction "NC_4_5") (pintype "no_connect"))
    )
    (net (code "57") (name "unconnected-(CR1-NC_5-Pad7)") (class "Default")
      (node (ref "CR1") (pin "7") (pinfunction "NC_5_7") (pintype "no_connect"))
    )
    (net (code "58") (name "unconnected-(IC2-N.C.-Pad2)") (class "Default")
      (node (ref "IC2") (pin "2") (pinfunction "N.C._2") (pintype "no_connect"))
    )
    (net (code "59") (name "unconnected-(U1-PA1-Pad11)") (class "Default")
      (node (ref "U1") (pin "11") (pinfunction "PA1_11") (pintype "bidirectional"))
    )
    (net (code "60") (name "unconnected-(U1-PA3-Pad13)") (class "Default")
      (node (ref "U1") (pin "13") (pinfunction "PA3_13") (pintype "bidirectional"))
    )
    (net (code "61") (name "unconnected-(U1-PA8-Pad29)") (class "Default")
      (node (ref "U1") (pin "29") (pinfunction "PA8_29") (pintype "bidirectional"))
    )
    (net (code "62") (name "unconnected-(U1-PA9-Pad30)") (class "Default")
      (node (ref "U1") (pin "30") (pinfunction "PA9_30") (pintype "bidirectional"))
    )
    (net (code "63") (name "unconnected-(U1-PA10-Pad31)") (class "Default")
      (node (ref "U1") (pin "31") (pinfunction "PA10_31") (pintype "bidirectional"))
    )
    (net (code "64") (name "unconnected-(U1-PA11-Pad32)") (class "Default")
      (node (ref "U1") (pin "32") (pinfunction "PA11_32") (pintype "bidirectional"))
    )
    (net (code "65") (name "unconnected-(U1-PA12-Pad33)") (class "Default")
      (node (ref "U1") (pin "33") (pinfunction "PA12_33") (pintype "bidirectional"))
    )
    (net (code "66") (name "unconnected-(U1-PA15-Pad38)") (class "Default")
      (node (ref "U1") (pin "38") (pinfunction "PA15_38") (pintype "bidirectional"))
    )
    (net (code "67") (name "unconnected-(U1-PB1-Pad19)") (class "Default")
      (node (ref "U1") (pin "19") (pinfunction "PB1_19") (pintype "bidirectional"))
    )
    (net (code "68") (name "unconnected-(U1-PB2-Pad20)") (class "Default")
      (node (ref "U1") (pin "20") (pinfunction "PB2_20") (pintype "bidirectional"))
    )
    (net (code "69") (name "unconnected-(U1-PB3-Pad39)") (class "Default")
      (node (ref "U1") (pin "39") (pinfunction "PB3_39") (pintype "bidirectional"))
    )
    (net (code "70") (name "unconnected-(U1-PB4-Pad40)") (class "Default")
      (node (ref "U1") (pin "40") (pinfunction "PB4_40") (pintype "bidirectional"))
    )
    (net (code "71") (name "unconnected-(U1-PB6-Pad42)") (class "Default")
      (node (ref "U1") (pin "42") (pinfunction "PB6_42") (pintype "bidirectional"))
    )
    (net (code "72") (name "unconnected-(U1-PB7-Pad43)") (class "Default")
      (node (ref "U1") (pin "43") (pinfunction "PB7_43") (pintype "bidirectional"))
    )
    (net (code "73") (name "unconnected-(U1-PB8-Pad45)") (class "Default")
      (node (ref "U1") (pin "45") (pinfunction "PB8_45") (pintype "bidirectional"))
    )
    (net (code "74") (name "unconnected-(U1-PB9-Pad46)") (class "Default")
      (node (ref "U1") (pin "46") (pinfunction "PB9_46") (pintype "bidirectional"))
    )
    (net (code "75") (name "unconnected-(U1-PB10-Pad21)") (class "Default")
      (node (ref "U1") (pin "21") (pinfunction "PB10_21") (pintype "bidirectional"))
    )
    (net (code "76") (name "unconnected-(U1-PC13-Pad2)") (class "Default")
      (node (ref "U1") (pin "2") (pinfunction "PC13_2") (pintype "bidirectional"))
    )
    (net (code "77") (name "unconnected-(U1-PC14{slash}OSC32_IN-Pad3)") (class "Default")
      (node (ref "U1") (pin "3") (pinfunction "PC14/OSC32_IN_3") (pintype "bidirectional"))
    )
    (net (code "78") (name "unconnected-(U1-PC15{slash}OSC32_OUT-Pad4)") (class "Default")
      (node (ref "U1") (pin "4") (pinfunction "PC15/OSC32_OUT_4") (pintype "bidirectional"))
    )
    (net (code "79") (name "unconnected-(U1-PH0{slash}OSC_IN-Pad5)") (class "Default")
      (node (ref "U1") (pin "5") (pinfunction "PH0/OSC_IN_5") (pintype "bidirectional"))
    )
    (net (code "80") (name "unconnected-(U1-PH1{slash}OSC_OUT-Pad6)") (class "Default")
      (node (ref "U1") (pin "6") (pinfunction "PH1/OSC_OUT_6") (pintype "bidirectional"))
    )
    (net (code "81") (name "unconnected-(U2-N{slash}C-Pad4)") (class "Default")
      (node (ref "U2") (pin "4") (pinfunction "N/C_4") (pintype "no_connect"))
    )
    (net (code "82") (name "unconnected-(U3-DNC-Pad8)") (class "Default")
      (node (ref "U3") (pin "8") (pinfunction "DNC_8") (pintype "passive"))
    )
    (net (code "83") (name "unconnected-(U3-DNC_2-Pad1)") (class "Default")
      (node (ref "U3") (pin "1") (pinfunction "DNC_2_1") (pintype "passive"))
    )
    (net (code "84") (name "unconnected-(U3-NC-Pad7)") (class "Default")
      (node (ref "U3") (pin "7") (pinfunction "NC_7") (pintype "no_connect"))
    )
    (net (code "85") (name "unconnected-(U3-TEMP-Pad3)") (class "Default")
      (node (ref "U3") (pin "3") (pinfunction "TEMP_3") (pintype "passive"))
    )
    (net (code "86") (name "unconnected-(U5-RG-Pad8)") (class "Default")
      (node (ref "U5") (pin "8") (pinfunction "RG_8") (pintype "passive"))
    )
    (net (code "87") (name "unconnected-(U5-RG_2-Pad1)") (class "Default")
      (node (ref "U5") (pin "1") (pinfunction "RG_2_1") (pintype "passive"))
    )
    (net (code "88") (name "unconnected-(U6-NC-Pad5)") (class "Default")
      (node (ref "U6") (pin "5") (pinfunction "NC_5") (pintype "passive"))
    )
    (net (code "89") (name "unconnected-(U6-NC_2-Pad1)") (class "Default")
      (node (ref "U6") (pin "1") (pinfunction "NC_2_1") (pintype "passive"))
    )
    (net (code "90") (name "unconnected-(U6-PadEPAD)") (class "Default")
      (node (ref "U6") (pin "EPAD") (pinfunction "EPAD_EPAD") (pintype "passive"))
    )
  )
)
